# CAN_5V.net
KiCad netlist of a schematic drawn in Altium Designer
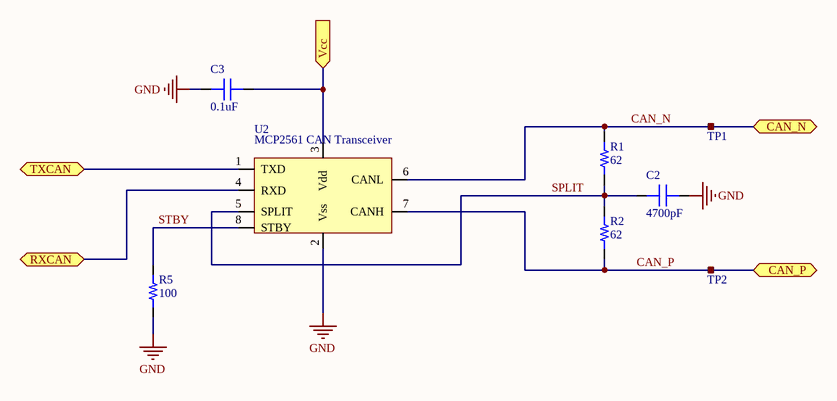
[diagram p0: CAN_5V.SchDoc]

(export (version "E")
  (design (tool "Eeschema 10.0.6"))
  (components
    (comp (ref "C2")
      (value "capacitor")
      (footprint "0603")
      (description "Generic 0603 capacitor")
      (fields (field (name "CAPACITANCE") "4700pF") (field (name "VOLTAGE") "50"))
      (libsource (lib "altlib") (part "capacitor"))
    )
    (comp (ref "C3")
      (value "capacitor")
      (footprint "0603")
      (description "Generic 0603 capacitor")
      (fields (field (name "CAPACITANCE") "0.1uF") (field (name "VOLTAGE") "50"))
      (libsource (lib "altlib") (part "capacitor"))
    )
    (comp (ref "R1")
      (value "62")
      (footprint "RES 0603/1608")
      (fields (field (name "RESISTANCE") "62"))
      (libsource (lib "altlib") (part "Resistor"))
    )
    (comp (ref "R2")
      (value "resistor")
      (footprint "0603")
      (fields (field (name "RESISTANCE") "62"))
      (libsource (lib "altlib") (part "resistor"))
    )
    (comp (ref "R5")
      (value "resistor")
      (footprint "0603")
      (fields (field (name "RESISTANCE") "100"))
      (libsource (lib "altlib") (part "resistor"))
    )
    (comp (ref "TP1") (value "RCU-0C") (footprint "RCU-0C") (libsource (lib "altlib") (part "RCU-0C")))
    (comp (ref "TP2") (value "RCU-0C") (footprint "RCU-0C") (libsource (lib "altlib") (part "RCU-0C")))
    (comp (ref "U2")
      (value "MCP2561 CAN Transceiver")
      (footprint "SOIC-8")
      (libsource (lib "altlib") (part "MCP2561 CAN Transceiver"))
    )
  )
  (nets
    (net (code "1") (name "/CAN_N") (class "Default")
      (node (ref "R1") (pin "2") (pinfunction "2_2") (pintype "passive"))
      (node (ref "TP1") (pin "1") (pintype "passive"))
      (node (ref "U2") (pin "6") (pinfunction "CANL_6") (pintype "passive"))
    )
    (net (code "2") (name "/CAN_P") (class "Default")
      (node (ref "R2") (pin "2") (pinfunction "2_2") (pintype "passive"))
      (node (ref "TP2") (pin "1") (pintype "passive"))
      (node (ref "U2") (pin "7") (pinfunction "CANH_7") (pintype "passive"))
    )
    (net (code "3") (name "/RXCAN") (class "Default")
      (node (ref "U2") (pin "4") (pinfunction "RXD_4") (pintype "passive"))
    )
    (net (code "4") (name "/SPLIT") (class "Default")
      (node (ref "C2") (pin "1") (pinfunction "1_1") (pintype "passive"))
      (node (ref "R1") (pin "1") (pinfunction "1_1") (pintype "passive"))
      (node (ref "R2") (pin "1") (pinfunction "1_1") (pintype "passive"))
      (node (ref "U2") (pin "5") (pinfunction "SPLIT_5") (pintype "passive"))
    )
    (net (code "5") (name "/STBY") (class "Default")
      (node (ref "R5") (pin "1") (pinfunction "1_1") (pintype "passive"))
      (node (ref "U2") (pin "8") (pinfunction "STBY_8") (pintype "passive"))
    )
    (net (code "6") (name "/TXCAN") (class "Default")
      (node (ref "U2") (pin "1") (pinfunction "TXD_1") (pintype "passive"))
    )
    (net (code "7") (name "/Vcc") (class "Default")
      (node (ref "C3") (pin "2") (pinfunction "2_2") (pintype "passive"))
      (node (ref "U2") (pin "3") (pinfunction "Vdd_3") (pintype "passive"))
    )
    (net (code "8") (name "GND") (class "Default")
      (node (ref "C2") (pin "2") (pinfunction "2_2") (pintype "passive"))
      (node (ref "C3") (pin "1") (pinfunction "1_1") (pintype "passive"))
      (node (ref "R5") (pin "2") (pinfunction "2_2") (pintype "passive"))
      (node (ref "U2") (pin "2") (pinfunction "Vss_2") (pintype "passive"))
    )
  )
)
